# RV09-S_v2_SCH.net
KiCad netlist of a schematic drawn in Altium Designer
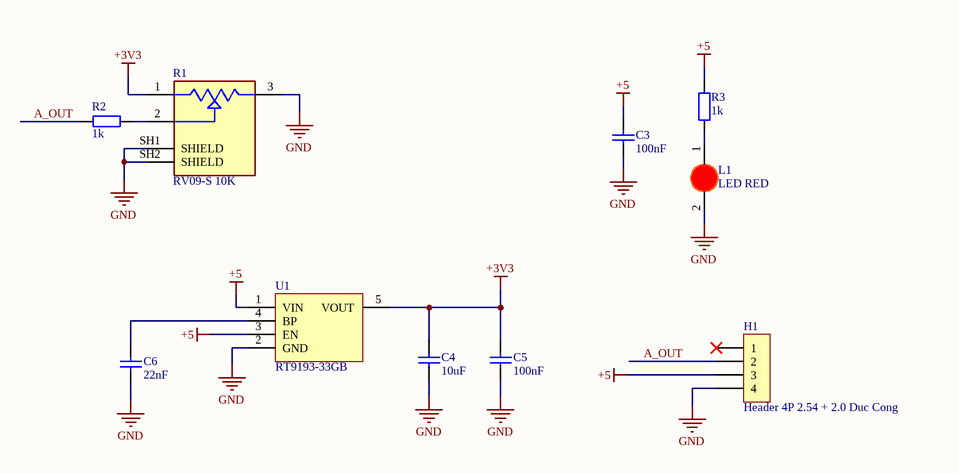
[diagram p0: RV09-S_v2_SCH.SchDoc]

(export (version "E")
  (design (tool "Eeschema 10.0.6"))
  (components
    (comp (ref "C3")
      (value "100nF")
      (footprint "tu 0603")
      (description "Dán")
      (libsource (lib "namnt_Lib") (part "Tu 0603 104 50V 10%"))
    )
    (comp (ref "C4")
      (value "10uF")
      (footprint "tu 0603")
      (description "Dán")
      (libsource (lib "namnt_Lib") (part "Tu 0603 106 16V 20%"))
    )
    (comp (ref "C5")
      (value "100nF")
      (footprint "tu 0603")
      (description "Dán")
      (libsource (lib "namnt_Lib") (part "Tu 0603 104 50V 10%"))
    )
    (comp (ref "C6")
      (value "22nF")
      (footprint "tu 0603")
      (description "Dán")
      (libsource (lib "namnt_Lib") (part "Tu 0603 104 50V 10%"))
    )
    (comp (ref "H1")
      (value "Header 4P 2.54 + 2.0 Duc Cong")
      (footprint "Header 4P DC 2.54 + 2.0")
      (description "Cắm")
      (libsource (lib "namnt_Lib") (part "Header 4P 2.54 + 2.0 Duc Cong"))
    )
    (comp (ref "L1")
      (value "LED RED")
      (footprint "LED-0805-Red")
      (description "Dán")
      (libsource (lib "namnt_Lib") (part "LED 0805 Do"))
    )
    (comp (ref "R1")
      (value "RV09-S 10K")
      (footprint "TRIM_RV09AF-40-20K-A10K")
      (fields (field (name "MF") "Alpha Taiwan") (field (name "MP") "RV09AF-40-20K-A10K"))
      (libsource (lib "namnt_Lib") (part "RV09-S 10k"))
    )
    (comp (ref "R2")
      (value "1k")
      (footprint "tro smd 0603")
      (description "Dán")
      (libsource (lib "namnt_Lib") (part "Tro 0603 1% 10k"))
    )
    (comp (ref "R3")
      (value "1k")
      (footprint "tro smd 0603")
      (description "Dán")
      (libsource (lib "namnt_Lib") (part "Tro 0603 1% 1k"))
    )
    (comp (ref "U1")
      (value "RT9193-33GB")
      (footprint "SOT23-5")
      (description "Linear Voltage Regulator IC 1 Output 300mA SOT-23-5")
      (fields (field (name "MANUFACTURER") "Richtek USA Inc."))
      (libsource (lib "namnt_Lib") (part "REG_5.5V-3.3V-0.3A-1W-SOT-23-5"))
    )
  )
  (nets
    (net (code "1") (name "+3V3") (class "Default")
      (node (ref "C4") (pin "1") (pinfunction "1_1") (pintype "passive"))
      (node (ref "C5") (pin "1") (pinfunction "1_1") (pintype "passive"))
      (node (ref "R1") (pin "1") (pinfunction "1_1") (pintype "passive"))
      (node (ref "U1") (pin "5") (pinfunction "VOUT_5") (pintype "passive"))
    )
    (net (code "2") (name "+5") (class "Default")
      (node (ref "C3") (pin "1") (pinfunction "1_1") (pintype "passive"))
      (node (ref "H1") (pin "3") (pinfunction "3_3") (pintype "passive"))
      (node (ref "R3") (pin "2") (pinfunction "2_2") (pintype "passive"))
      (node (ref "U1") (pin "1") (pinfunction "VIN_1") (pintype "passive"))
      (node (ref "U1") (pin "3") (pinfunction "EN_3") (pintype "passive"))
    )
    (net (code "3") (name "/A_OUT") (class "Default")
      (node (ref "H1") (pin "2") (pinfunction "2_2") (pintype "passive"))
      (node (ref "R2") (pin "2") (pinfunction "2_2") (pintype "passive"))
    )
    (net (code "4") (name "GND") (class "Default")
      (node (ref "C3") (pin "2") (pinfunction "2_2") (pintype "passive"))
      (node (ref "C4") (pin "2") (pinfunction "2_2") (pintype "passive"))
      (node (ref "C5") (pin "2") (pinfunction "2_2") (pintype "passive"))
      (node (ref "C6") (pin "2") (pinfunction "2_2") (pintype "passive"))
      (node (ref "H1") (pin "4") (pinfunction "4_4") (pintype "passive"))
      (node (ref "L1") (pin "2") (pinfunction "K_2") (pintype "passive"))
      (node (ref "R1") (pin "3") (pinfunction "3_3") (pintype "passive"))
      (node (ref "R1") (pin "SH1") (pinfunction "SHIELD_SH1") (pintype "passive"))
      (node (ref "R1") (pin "SH2") (pinfunction "SHIELD_SH2") (pintype "passive"))
      (node (ref "U1") (pin "2") (pinfunction "GND_2") (pintype "passive"))
    )
    (net (code "5") (name "Net-(L1-A)") (class "Default")
      (node (ref "L1") (pin "1") (pinfunction "A_1") (pintype "passive"))
      (node (ref "R3") (pin "1") (pinfunction "1_1") (pintype "passive"))
    )
    (net (code "6") (name "Net-(R1-Pad2)") (class "Default")
      (node (ref "R1") (pin "2") (pinfunction "2_2") (pintype "passive"))
      (node (ref "R2") (pin "1") (pinfunction "1_1") (pintype "passive"))
    )
    (net (code "7") (name "Net-(U1-BP)") (class "Default")
      (node (ref "C6") (pin "1") (pinfunction "1_1") (pintype "passive"))
      (node (ref "U1") (pin "4") (pinfunction "BP_4") (pintype "passive"))
    )
    (net (code "8") (name "unconnected-(H1-Pad1)") (class "Default")
      (node (ref "H1") (pin "1") (pinfunction "1_1") (pintype "passive+no_connect"))
    )
  )
)
